# Front_right_lamp_v1.net
KiCad netlist of a schematic drawn in EAGLE
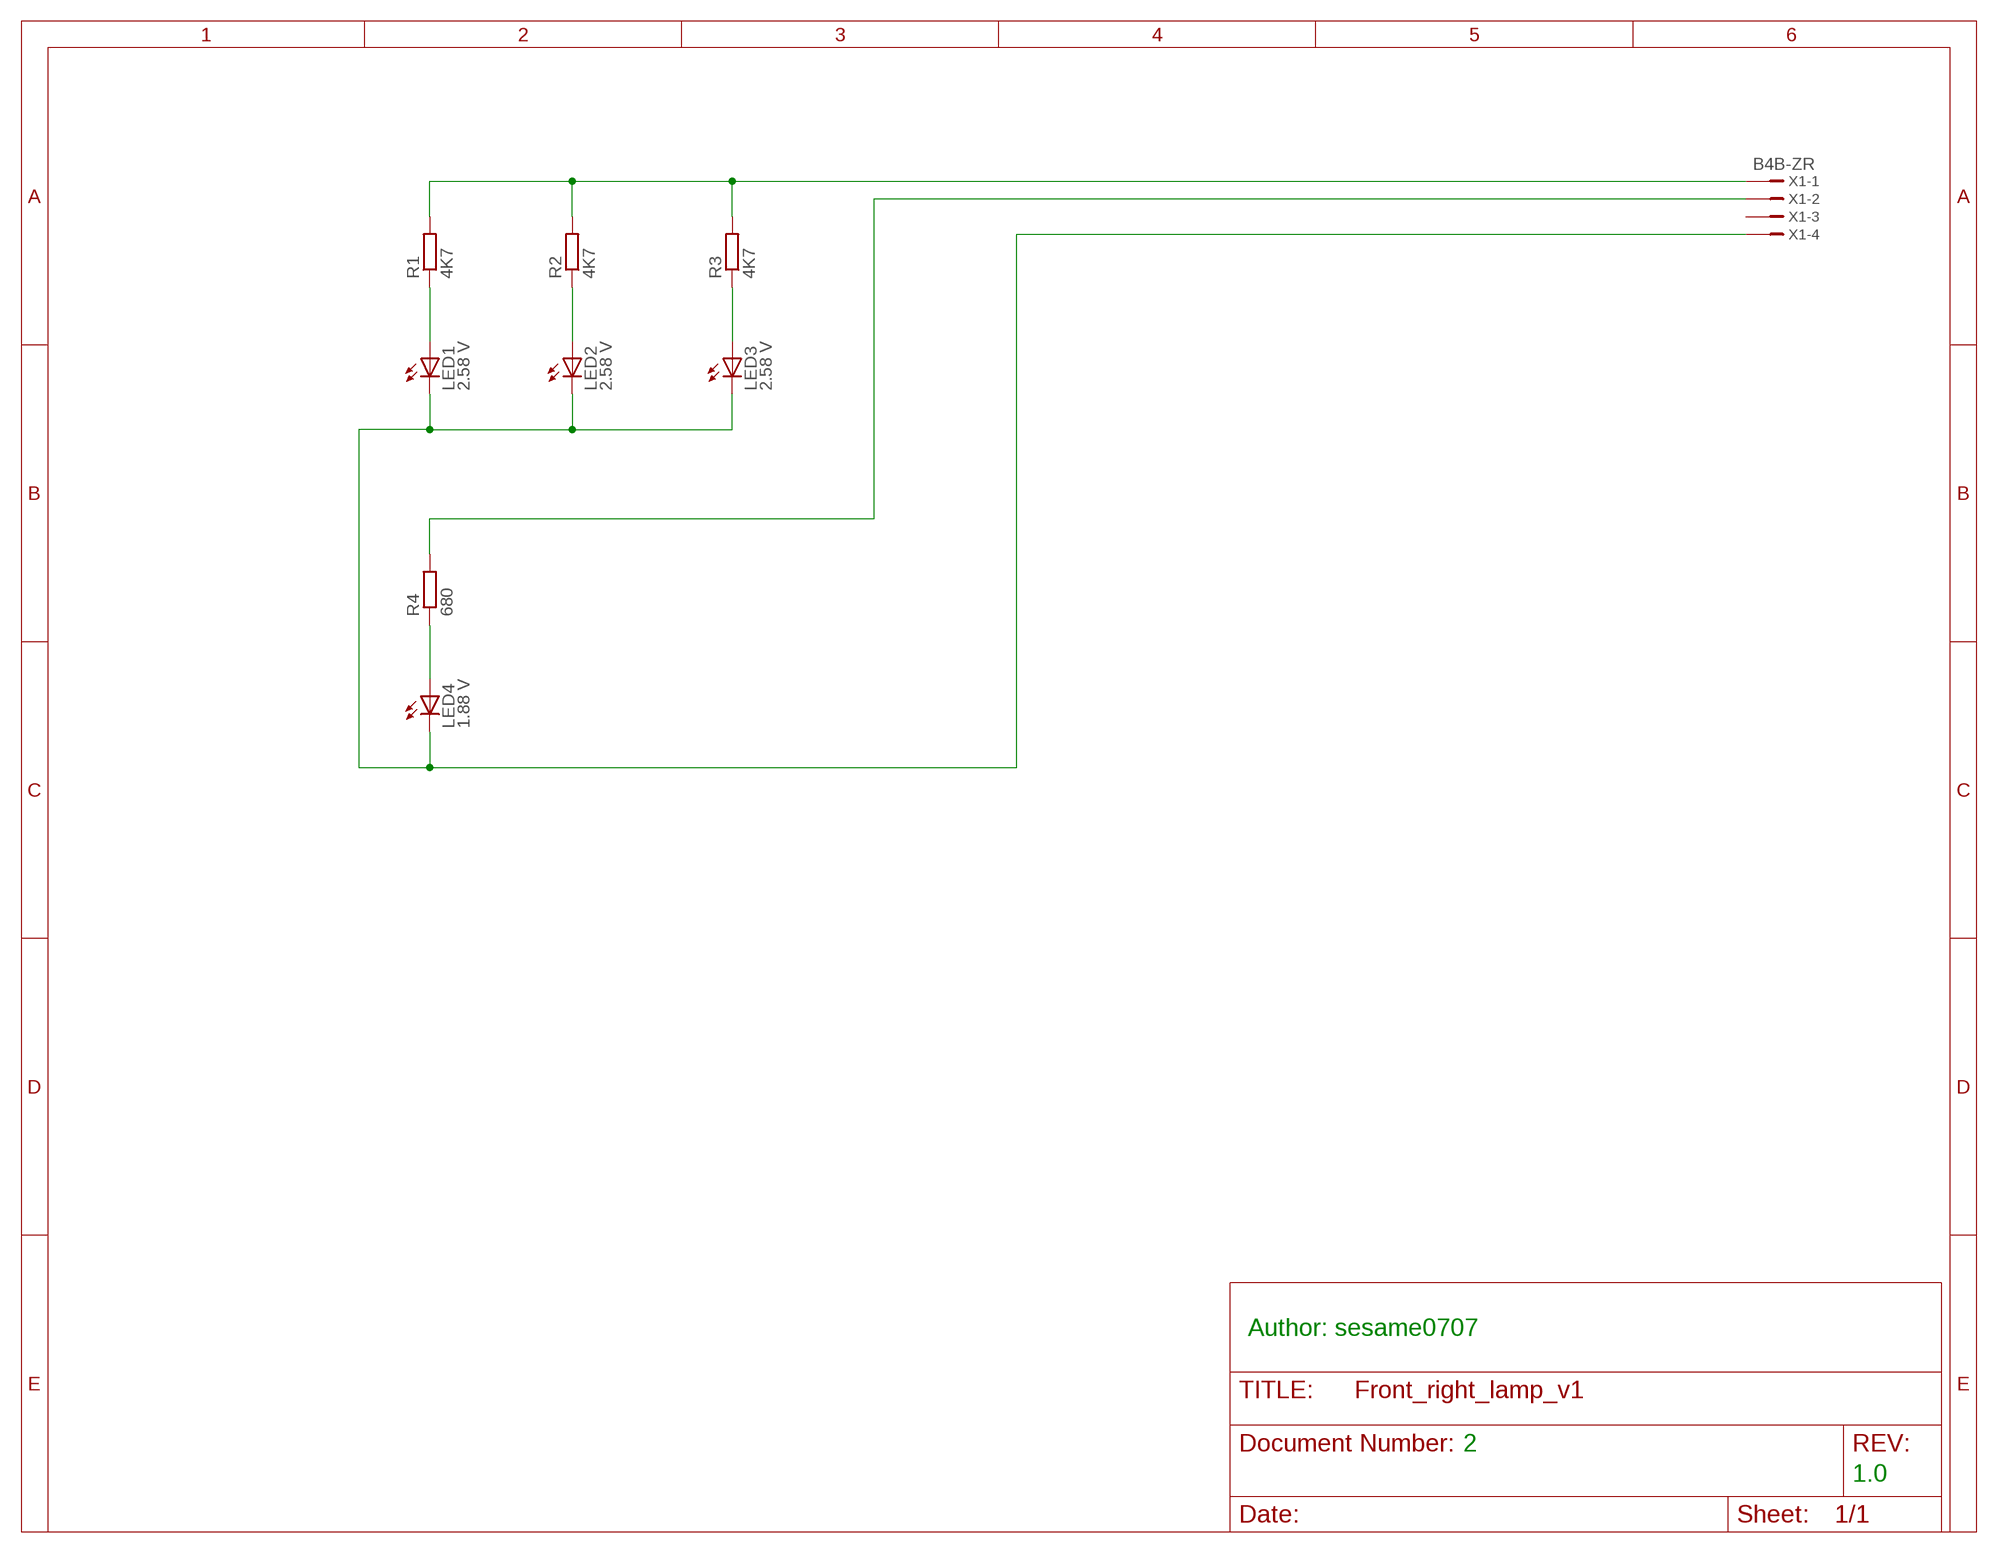
[diagram p0: schematic, sheet 1]

(export (version "E")
  (design (tool "Eeschema 10.0.6"))
  (components
    (comp (ref "LED1")
      (value "2.58 V")
      (footprint "eagle-import:LED5MM")
      (libsource (lib "eagle-import") (part "LED5MM"))
    )
    (comp (ref "LED2")
      (value "2.58 V")
      (footprint "eagle-import:LED5MM")
      (libsource (lib "eagle-import") (part "LED5MM"))
    )
    (comp (ref "LED3")
      (value "2.58 V")
      (footprint "eagle-import:LED5MM")
      (libsource (lib "eagle-import") (part "LED5MM"))
    )
    (comp (ref "LED4")
      (value "1.88 V")
      (footprint "eagle-import:LED5MM")
      (libsource (lib "eagle-import") (part "LED5MM"))
    )
    (comp (ref "R1")
      (value "4K7")
      (footprint "eagle-import:0204V")
      (libsource (lib "eagle-import") (part "R-EU_0204/2V"))
    )
    (comp (ref "R2")
      (value "4K7")
      (footprint "eagle-import:0204V")
      (libsource (lib "eagle-import") (part "R-EU_0204/2V"))
    )
    (comp (ref "R3")
      (value "4K7")
      (footprint "eagle-import:0204V")
      (libsource (lib "eagle-import") (part "R-EU_0204/2V"))
    )
    (comp (ref "R4")
      (value "680")
      (footprint "eagle-import:0204V")
      (libsource (lib "eagle-import") (part "R-EU_0204/2V"))
    )
    (comp (ref "X1")
      (value "B4B-ZR")
      (footprint "eagle-import:B4B-ZR")
      (fields (field (name "MF") "FARNELL") (field (name "MPN") "B4B-ZR(LF)(SN)"))
      (libsource (lib "eagle-import") (part "?4B-ZRB"))
    )
  )
  (nets
    (net (code "1") (name "Net-(LED1-C)") (class "Default")
      (node (ref "LED1") (pin "K") (pinfunction "C_K") (pintype "passive"))
      (node (ref "LED2") (pin "K") (pinfunction "C_K") (pintype "passive"))
      (node (ref "LED3") (pin "K") (pinfunction "C_K") (pintype "passive"))
      (node (ref "LED4") (pin "K") (pinfunction "C_K") (pintype "passive"))
      (node (ref "X1") (pin "4") (pinfunction "1_4") (pintype "passive"))
    )
    (net (code "2") (name "Net-(LED1-PadA)") (class "Default")
      (node (ref "LED1") (pin "A") (pinfunction "A_A") (pintype "passive"))
      (node (ref "R1") (pin "1") (pinfunction "1_1") (pintype "passive"))
    )
    (net (code "3") (name "Net-(LED2-PadA)") (class "Default")
      (node (ref "LED2") (pin "A") (pinfunction "A_A") (pintype "passive"))
      (node (ref "R2") (pin "1") (pinfunction "1_1") (pintype "passive"))
    )
    (net (code "4") (name "Net-(LED3-PadA)") (class "Default")
      (node (ref "LED3") (pin "A") (pinfunction "A_A") (pintype "passive"))
      (node (ref "R3") (pin "1") (pinfunction "1_1") (pintype "passive"))
    )
    (net (code "5") (name "Net-(LED4-PadA)") (class "Default")
      (node (ref "LED4") (pin "A") (pinfunction "A_A") (pintype "passive"))
      (node (ref "R4") (pin "1") (pinfunction "1_1") (pintype "passive"))
    )
    (net (code "6") (name "Net-(R1-Pad2)") (class "Default")
      (node (ref "R1") (pin "2") (pinfunction "2_2") (pintype "passive"))
      (node (ref "R2") (pin "2") (pinfunction "2_2") (pintype "passive"))
      (node (ref "R3") (pin "2") (pinfunction "2_2") (pintype "passive"))
      (node (ref "X1") (pin "1") (pinfunction "1_1") (pintype "passive"))
    )
    (net (code "7") (name "Net-(X1B-1)") (class "Default")
      (node (ref "R4") (pin "2") (pinfunction "2_2") (pintype "passive"))
      (node (ref "X1") (pin "2") (pinfunction "1_2") (pintype "passive"))
    )
    (net (code "8") (name "unconnected-(X1C-1-Pad3)") (class "Default")
      (node (ref "X1") (pin "3") (pinfunction "1_3") (pintype "passive"))
    )
  )
)
